# BufferBias.net
KiCad netlist of a schematic drawn in Altium Designer
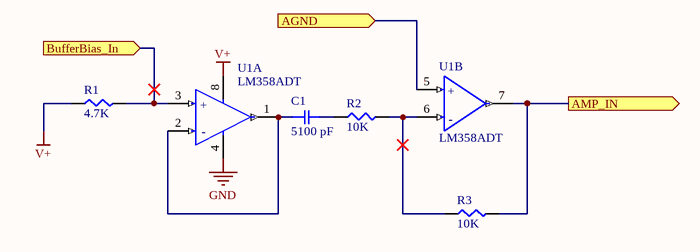
[diagram p0: BufferBias.SchDoc]

(export (version "E")
  (design (tool "Eeschema 10.0.6"))
  (components
    (comp (ref "C1")
      (value "5100 pF")
      (footprint "SMD-0805C")
      (fields
        (field (name "MANUFACTURER") "KEMET")
        (field (name "MANUFACTURER PART NUMBER") "C0805C512F4HACAUTO")
      )
      (libsource (lib "capacitor_murata_0805") (part "GRM2195C1H512JA01D"))
    )
    (comp (ref "R1")
      (value "4.7K")
      (footprint "SMD-0805-RES")
      (fields
        (field (name "MANUFACTURER") "Stackpole Electronics Inc")
        (field (name "MANUFACTURER PART NUMBER") "RNCF0805DTE4K70")
      )
      (libsource (lib "Panasonic_resistor_0805") (part "ERJ-6ENF4701V"))
    )
    (comp (ref "R2")
      (value "10K")
      (footprint "SMD-0805-RES")
      (fields
        (field (name "MANUFACTURER") "Stackpole Electronics Inc")
        (field (name "MANUFACTURER PART NUMBER") "RMCF0805JG10K0")
      )
      (libsource (lib "Panasonic_resistor_0805") (part "ERJ-6ENF1002V"))
    )
    (comp (ref "R3")
      (value "10K")
      (footprint "SMD-0805-RES")
      (fields
        (field (name "MANUFACTURER") "Stackpole Electronics Inc")
        (field (name "MANUFACTURER PART NUMBER") "RMCF0805JG10K0")
      )
      (libsource (lib "Panasonic_resistor_0805") (part "ERJ-6ENF1002V"))
    )
    (comp (ref "U1")
      (value "LM358ADT")
      (footprint "FP-SO8-IPC_C")
      (fields
        (field (name "MANUFACTURER") "STMicroelectronics")
        (field (name "MANUFACTURER PART NUMBER") "LM358WDT")
      )
      (libsource (lib "Altium Content Vault") (part "9f386d5a0a155305257da89b0c2f71e"))
    )
  )
  (nets
    (net (code "1") (name "/AGND") (class "Default")
      (node (ref "U1") (pin "5") (pinfunction "In2+_5") (pintype "input"))
    )
    (net (code "2") (name "/AMP_IN") (class "Default")
      (node (ref "R3") (pin "2") (pinfunction "2_2") (pintype "passive"))
      (node (ref "U1") (pin "7") (pinfunction "Out2_7") (pintype "output"))
    )
    (net (code "3") (name "/BufferBias_In") (class "Default")
      (node (ref "R1") (pin "2") (pinfunction "2_2") (pintype "passive"))
      (node (ref "U1") (pin "3") (pinfunction "In1+_3") (pintype "input"))
    )
    (net (code "4") (name "GND") (class "Default")
      (node (ref "U1") (pin "4") (pinfunction "VCC-_4") (pintype "power_in"))
    )
    (net (code "5") (name "Net-(C1-Pad2)") (class "Default")
      (node (ref "C1") (pin "2") (pinfunction "2_2") (pintype "passive"))
      (node (ref "R2") (pin "1") (pinfunction "1_1") (pintype "passive"))
    )
    (net (code "6") (name "Net-(U1A-In1-)") (class "Default")
      (node (ref "C1") (pin "1") (pinfunction "1_1") (pintype "passive"))
      (node (ref "U1") (pin "1") (pinfunction "Out1_1") (pintype "passive"))
      (node (ref "U1") (pin "2") (pinfunction "In1-_2") (pintype "input"))
    )
    (net (code "7") (name "Net-(U1B-In2-)") (class "Default")
      (node (ref "R2") (pin "2") (pinfunction "2_2") (pintype "passive"))
      (node (ref "R3") (pin "1") (pinfunction "1_1") (pintype "passive"))
      (node (ref "U1") (pin "6") (pinfunction "In2-_6") (pintype "input"))
    )
    (net (code "8") (name "V+") (class "Default")
      (node (ref "R1") (pin "1") (pinfunction "1_1") (pintype "passive"))
      (node (ref "U1") (pin "8") (pinfunction "VCC+_8") (pintype "power_in"))
    )
  )
)
